# Vref_1.net
KiCad netlist of a schematic drawn in Altium Designer
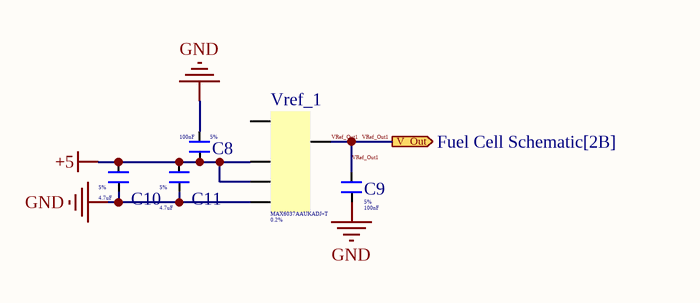
[diagram p0: Vref_1.SchDoc]

(export (version "E")
  (design (tool "Eeschema 10.0.6"))
  (components
    (comp (ref "C8")
      (value "~")
      (footprint "Capacitor_Kemet_0805")
      (description "Cap Ceramic 0.1uF 16V X7R 5% SMD 0805 125°C Plastic T/R")
      (fields
        (field (name "MANUFACTURER") "KEMET")
        (field (name "MANUFACTURER PART NUMBER") "C0805C104J4RACTU")
        (field (name "DISSIPATION FACTOR") "5%")
        (field (name "CAPACITANCE") "100nF")
      )
      (libsource (lib "Schlib1") (part "C0805C104J4RACTU"))
    )
    (comp (ref "C9")
      (value "~")
      (footprint "Capacitor_Kemet_0805")
      (description "Cap Ceramic 0.1uF 16V X7R 5% SMD 0805 125°C Plastic T/R")
      (fields
        (field (name "MANUFACTURER") "KEMET")
        (field (name "MANUFACTURER PART NUMBER") "C0805C104J4RACTU")
        (field (name "DISSIPATION FACTOR") "5%")
        (field (name "CAPACITANCE") "100nF")
      )
      (libsource (lib "Schlib1") (part "C0805C104J4RACTU"))
    )
    (comp (ref "C10")
      (value "~")
      (footprint "Capacitor_Kemet_0805")
      (description "CAP CER 4.7UF 16V X7R 0805")
      (fields
        (field (name "MANUFACTURER") "KEMET")
        (field (name "MANUFACTURER PART NUMBER") "C0805C475J4RACAUTO")
        (field (name "TOLERANCE") "5%")
        (field (name "CAPACITANCE") "4.7uF")
      )
      (libsource (lib "Schlib1") (part "C0805C475J4RACAUTO"))
    )
    (comp (ref "C11")
      (value "~")
      (footprint "Capacitor_Kemet_0805")
      (description "CAP CER 4.7UF 16V X7R 0805")
      (fields
        (field (name "MANUFACTURER") "KEMET")
        (field (name "MANUFACTURER PART NUMBER") "C0805C475J4RACAUTO")
        (field (name "TOLERANCE") "5%")
        (field (name "CAPACITANCE") "4.7uF")
      )
      (libsource (lib "Schlib1") (part "C0805C475J4RACAUTO"))
    )
    (comp (ref "Vref_1")
      (value "~")
      (footprint "VRef")
      (description "IC VREF SERIES ADJ 0.2% SOT23-5")
      (fields
        (field (name "MANUFACTURER") "Maxim")
        (field (name "MANUFACTURER PART NUMBER") "MAX6037AAUKADJ+T")
        (field (name "TOLERANCE") "0.2%")
      )
      (libsource (lib "Schlib1") (part "MAX6037AAUKADJ+T"))
    )
  )
  (nets
    (net (code "1") (name "+5") (class "Default")
      (node (ref "C10") (pin "2") (pinfunction "2_2") (pintype "passive"))
      (node (ref "C11") (pin "2") (pinfunction "2_2") (pintype "passive"))
      (node (ref "C8") (pin "1") (pinfunction "1_1") (pintype "passive"))
      (node (ref "Vref_1") (pin "3") (pinfunction "SHDN_3") (pintype "passive"))
      (node (ref "Vref_1") (pin "4") (pinfunction "In_4") (pintype "passive"))
    )
    (net (code "2") (name "/VRef_Out1") (class "Default")
      (node (ref "C9") (pin "2") (pinfunction "2_2") (pintype "passive"))
      (node (ref "Vref_1") (pin "5") (pinfunction "OUT_5") (pintype "passive"))
    )
    (net (code "3") (name "GND") (class "Default")
      (node (ref "C10") (pin "1") (pinfunction "1_1") (pintype "passive"))
      (node (ref "C11") (pin "1") (pinfunction "1_1") (pintype "passive"))
      (node (ref "C8") (pin "2") (pinfunction "2_2") (pintype "passive"))
      (node (ref "C9") (pin "1") (pinfunction "1_1") (pintype "passive"))
      (node (ref "Vref_1") (pin "2") (pinfunction "GND_2") (pintype "passive"))
    )
    (net (code "4") (name "unconnected-(Vref_1-ADJ-Pad1)") (class "Default")
      (node (ref "Vref_1") (pin "1") (pinfunction "ADJ_1") (pintype "passive"))
    )
  )
)
